# Archive.net
KiCad netlist of a schematic drawn in Altium Designer
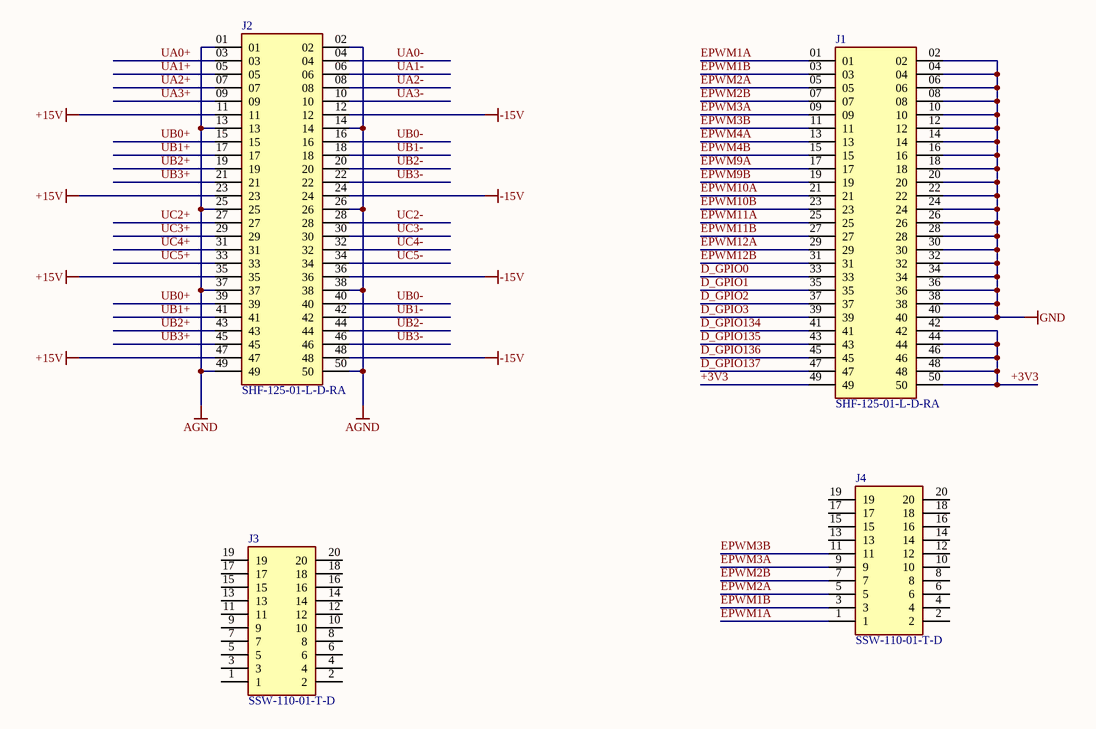
[diagram p0: Archive.SchDoc]

(export (version "E")
  (design (tool "Eeschema 10.0.6"))
  (components
    (comp (ref "J1")
      (value "SHF-125-01-L-D-RA")
      (footprint "SAMTEC_SHF-125-01-L-D-RA")
      (fields (field (name "MF") "Samtec"))
      (libsource (lib "FYP_Connectors") (part "SHF-125-01-L-D-RA"))
    )
    (comp (ref "J2")
      (value "SHF-125-01-L-D-RA")
      (footprint "SAMTEC_SHF-125-01-L-D-RA")
      (fields (field (name "MF") "Samtec"))
      (libsource (lib "FYP_Connectors") (part "SHF-125-01-L-D-RA"))
    )
    (comp (ref "J3")
      (value "SSW-110-01-T-D")
      (footprint "SamacSys:SAMTEC_SSW-110-01-T-D")
      (description "Connector")
      (fields (field (name "MOUSER PART NUMBER") "200-SSW11001TD"))
      (libsource (lib "FYP_Connectors") (part "SSW-110-01-T-D"))
    )
    (comp (ref "J4")
      (value "SSW-110-01-T-D")
      (footprint "SamacSys:SAMTEC_SSW-110-01-T-D")
      (description "Connector")
      (fields (field (name "MOUSER PART NUMBER") "200-SSW11001TD"))
      (libsource (lib "FYP_Connectors") (part "SSW-110-01-T-D"))
    )
  )
  (nets
    (net (code "1") (name "+15V") (class "Default")
      (node (ref "J2") (pin "11") (pinfunction "11_11") (pintype "passive"))
      (node (ref "J2") (pin "23") (pinfunction "23_23") (pintype "passive"))
      (node (ref "J2") (pin "35") (pinfunction "35_35") (pintype "passive"))
      (node (ref "J2") (pin "47") (pinfunction "47_47") (pintype "passive"))
    )
    (net (code "2") (name "-15V") (class "Default")
      (node (ref "J2") (pin "12") (pinfunction "12_12") (pintype "passive"))
      (node (ref "J2") (pin "24") (pinfunction "24_24") (pintype "passive"))
      (node (ref "J2") (pin "36") (pinfunction "36_36") (pintype "passive"))
      (node (ref "J2") (pin "48") (pinfunction "48_48") (pintype "passive"))
    )
    (net (code "3") (name "/+3V3") (class "Default")
      (node (ref "J1") (pin "42") (pinfunction "42_42") (pintype "passive"))
      (node (ref "J1") (pin "44") (pinfunction "44_44") (pintype "passive"))
      (node (ref "J1") (pin "46") (pinfunction "46_46") (pintype "passive"))
      (node (ref "J1") (pin "48") (pinfunction "48_48") (pintype "passive"))
      (node (ref "J1") (pin "49") (pinfunction "49_49") (pintype "passive"))
      (node (ref "J1") (pin "50") (pinfunction "50_50") (pintype "passive"))
    )
    (net (code "4") (name "/D_GPIO0") (class "Default")
      (node (ref "J1") (pin "33") (pinfunction "33_33") (pintype "passive"))
    )
    (net (code "5") (name "/D_GPIO1") (class "Default")
      (node (ref "J1") (pin "35") (pinfunction "35_35") (pintype "passive"))
    )
    (net (code "6") (name "/D_GPIO2") (class "Default")
      (node (ref "J1") (pin "37") (pinfunction "37_37") (pintype "passive"))
    )
    (net (code "7") (name "/D_GPIO3") (class "Default")
      (node (ref "J1") (pin "39") (pinfunction "39_39") (pintype "passive"))
    )
    (net (code "8") (name "/D_GPIO134") (class "Default")
      (node (ref "J1") (pin "41") (pinfunction "41_41") (pintype "passive"))
    )
    (net (code "9") (name "/D_GPIO135") (class "Default")
      (node (ref "J1") (pin "43") (pinfunction "43_43") (pintype "passive"))
    )
    (net (code "10") (name "/D_GPIO136") (class "Default")
      (node (ref "J1") (pin "45") (pinfunction "45_45") (pintype "passive"))
    )
    (net (code "11") (name "/D_GPIO137") (class "Default")
      (node (ref "J1") (pin "47") (pinfunction "47_47") (pintype "passive"))
    )
    (net (code "12") (name "/EPWM1A") (class "Default")
      (node (ref "J1") (pin "01") (pinfunction "01_01") (pintype "passive"))
      (node (ref "J4") (pin "1") (pinfunction "1_1") (pintype "passive"))
    )
    (net (code "13") (name "/EPWM1B") (class "Default")
      (node (ref "J1") (pin "03") (pinfunction "03_03") (pintype "passive"))
      (node (ref "J4") (pin "3") (pinfunction "3_3") (pintype "passive"))
    )
    (net (code "14") (name "/EPWM2A") (class "Default")
      (node (ref "J1") (pin "05") (pinfunction "05_05") (pintype "passive"))
      (node (ref "J4") (pin "5") (pinfunction "5_5") (pintype "passive"))
    )
    (net (code "15") (name "/EPWM2B") (class "Default")
      (node (ref "J1") (pin "07") (pinfunction "07_07") (pintype "passive"))
      (node (ref "J4") (pin "7") (pinfunction "7_7") (pintype "passive"))
    )
    (net (code "16") (name "/EPWM3A") (class "Default")
      (node (ref "J1") (pin "09") (pinfunction "09_09") (pintype "passive"))
      (node (ref "J4") (pin "9") (pinfunction "9_9") (pintype "passive"))
    )
    (net (code "17") (name "/EPWM3B") (class "Default")
      (node (ref "J1") (pin "11") (pinfunction "11_11") (pintype "passive"))
      (node (ref "J4") (pin "11") (pinfunction "11_11") (pintype "passive"))
    )
    (net (code "18") (name "/EPWM4A") (class "Default")
      (node (ref "J1") (pin "13") (pinfunction "13_13") (pintype "passive"))
    )
    (net (code "19") (name "/EPWM4B") (class "Default")
      (node (ref "J1") (pin "15") (pinfunction "15_15") (pintype "passive"))
    )
    (net (code "20") (name "/EPWM9A") (class "Default")
      (node (ref "J1") (pin "17") (pinfunction "17_17") (pintype "passive"))
    )
    (net (code "21") (name "/EPWM9B") (class "Default")
      (node (ref "J1") (pin "19") (pinfunction "19_19") (pintype "passive"))
    )
    (net (code "22") (name "/EPWM10A") (class "Default")
      (node (ref "J1") (pin "21") (pinfunction "21_21") (pintype "passive"))
    )
    (net (code "23") (name "/EPWM10B") (class "Default")
      (node (ref "J1") (pin "23") (pinfunction "23_23") (pintype "passive"))
    )
    (net (code "24") (name "/EPWM11A") (class "Default")
      (node (ref "J1") (pin "25") (pinfunction "25_25") (pintype "passive"))
    )
    (net (code "25") (name "/EPWM11B") (class "Default")
      (node (ref "J1") (pin "27") (pinfunction "27_27") (pintype "passive"))
    )
    (net (code "26") (name "/EPWM12A") (class "Default")
      (node (ref "J1") (pin "29") (pinfunction "29_29") (pintype "passive"))
    )
    (net (code "27") (name "/EPWM12B") (class "Default")
      (node (ref "J1") (pin "31") (pinfunction "31_31") (pintype "passive"))
    )
    (net (code "28") (name "/UA0+") (class "Default")
      (node (ref "J2") (pin "03") (pinfunction "03_03") (pintype "passive"))
    )
    (net (code "29") (name "/UA0-") (class "Default")
      (node (ref "J2") (pin "04") (pinfunction "04_04") (pintype "passive"))
    )
    (net (code "30") (name "/UA1+") (class "Default")
      (node (ref "J2") (pin "05") (pinfunction "05_05") (pintype "passive"))
    )
    (net (code "31") (name "/UA1-") (class "Default")
      (node (ref "J2") (pin "06") (pinfunction "06_06") (pintype "passive"))
    )
    (net (code "32") (name "/UA2+") (class "Default")
      (node (ref "J2") (pin "07") (pinfunction "07_07") (pintype "passive"))
    )
    (net (code "33") (name "/UA2-") (class "Default")
      (node (ref "J2") (pin "08") (pinfunction "08_08") (pintype "passive"))
    )
    (net (code "34") (name "/UA3+") (class "Default")
      (node (ref "J2") (pin "09") (pinfunction "09_09") (pintype "passive"))
    )
    (net (code "35") (name "/UA3-") (class "Default")
      (node (ref "J2") (pin "10") (pinfunction "10_10") (pintype "passive"))
    )
    (net (code "36") (name "/UB0+") (class "Default")
      (node (ref "J2") (pin "15") (pinfunction "15_15") (pintype "passive"))
      (node (ref "J2") (pin "39") (pinfunction "39_39") (pintype "passive"))
    )
    (net (code "37") (name "/UB0-") (class "Default")
      (node (ref "J2") (pin "16") (pinfunction "16_16") (pintype "passive"))
      (node (ref "J2") (pin "40") (pinfunction "40_40") (pintype "passive"))
    )
    (net (code "38") (name "/UB1+") (class "Default")
      (node (ref "J2") (pin "17") (pinfunction "17_17") (pintype "passive"))
      (node (ref "J2") (pin "41") (pinfunction "41_41") (pintype "passive"))
    )
    (net (code "39") (name "/UB1-") (class "Default")
      (node (ref "J2") (pin "18") (pinfunction "18_18") (pintype "passive"))
      (node (ref "J2") (pin "42") (pinfunction "42_42") (pintype "passive"))
    )
    (net (code "40") (name "/UB2+") (class "Default")
      (node (ref "J2") (pin "19") (pinfunction "19_19") (pintype "passive"))
      (node (ref "J2") (pin "43") (pinfunction "43_43") (pintype "passive"))
    )
    (net (code "41") (name "/UB2-") (class "Default")
      (node (ref "J2") (pin "20") (pinfunction "20_20") (pintype "passive"))
      (node (ref "J2") (pin "44") (pinfunction "44_44") (pintype "passive"))
    )
    (net (code "42") (name "/UB3+") (class "Default")
      (node (ref "J2") (pin "21") (pinfunction "21_21") (pintype "passive"))
      (node (ref "J2") (pin "45") (pinfunction "45_45") (pintype "passive"))
    )
    (net (code "43") (name "/UB3-") (class "Default")
      (node (ref "J2") (pin "22") (pinfunction "22_22") (pintype "passive"))
      (node (ref "J2") (pin "46") (pinfunction "46_46") (pintype "passive"))
    )
    (net (code "44") (name "/UC2+") (class "Default")
      (node (ref "J2") (pin "27") (pinfunction "27_27") (pintype "passive"))
    )
    (net (code "45") (name "/UC2-") (class "Default")
      (node (ref "J2") (pin "28") (pinfunction "28_28") (pintype "passive"))
    )
    (net (code "46") (name "/UC3+") (class "Default")
      (node (ref "J2") (pin "29") (pinfunction "29_29") (pintype "passive"))
    )
    (net (code "47") (name "/UC3-") (class "Default")
      (node (ref "J2") (pin "30") (pinfunction "30_30") (pintype "passive"))
    )
    (net (code "48") (name "/UC4+") (class "Default")
      (node (ref "J2") (pin "31") (pinfunction "31_31") (pintype "passive"))
    )
    (net (code "49") (name "/UC4-") (class "Default")
      (node (ref "J2") (pin "32") (pinfunction "32_32") (pintype "passive"))
    )
    (net (code "50") (name "/UC5+") (class "Default")
      (node (ref "J2") (pin "33") (pinfunction "33_33") (pintype "passive"))
    )
    (net (code "51") (name "/UC5-") (class "Default")
      (node (ref "J2") (pin "34") (pinfunction "34_34") (pintype "passive"))
    )
    (net (code "52") (name "AGND") (class "Default")
      (node (ref "J2") (pin "01") (pinfunction "01_01") (pintype "passive"))
      (node (ref "J2") (pin "02") (pinfunction "02_02") (pintype "passive"))
      (node (ref "J2") (pin "13") (pinfunction "13_13") (pintype "passive"))
      (node (ref "J2") (pin "14") (pinfunction "14_14") (pintype "passive"))
      (node (ref "J2") (pin "25") (pinfunction "25_25") (pintype "passive"))
      (node (ref "J2") (pin "26") (pinfunction "26_26") (pintype "passive"))
      (node (ref "J2") (pin "37") (pinfunction "37_37") (pintype "passive"))
      (node (ref "J2") (pin "38") (pinfunction "38_38") (pintype "passive"))
      (node (ref "J2") (pin "49") (pinfunction "49_49") (pintype "passive"))
      (node (ref "J2") (pin "50") (pinfunction "50_50") (pintype "passive"))
    )
    (net (code "53") (name "GND") (class "Default")
      (node (ref "J1") (pin "02") (pinfunction "02_02") (pintype "passive"))
      (node (ref "J1") (pin "04") (pinfunction "04_04") (pintype "passive"))
      (node (ref "J1") (pin "06") (pinfunction "06_06") (pintype "passive"))
      (node (ref "J1") (pin "08") (pinfunction "08_08") (pintype "passive"))
      (node (ref "J1") (pin "10") (pinfunction "10_10") (pintype "passive"))
      (node (ref "J1") (pin "12") (pinfunction "12_12") (pintype "passive"))
      (node (ref "J1") (pin "14") (pinfunction "14_14") (pintype "passive"))
      (node (ref "J1") (pin "16") (pinfunction "16_16") (pintype "passive"))
      (node (ref "J1") (pin "18") (pinfunction "18_18") (pintype "passive"))
      (node (ref "J1") (pin "20") (pinfunction "20_20") (pintype "passive"))
      (node (ref "J1") (pin "22") (pinfunction "22_22") (pintype "passive"))
      (node (ref "J1") (pin "24") (pinfunction "24_24") (pintype "passive"))
      (node (ref "J1") (pin "26") (pinfunction "26_26") (pintype "passive"))
      (node (ref "J1") (pin "28") (pinfunction "28_28") (pintype "passive"))
      (node (ref "J1") (pin "30") (pinfunction "30_30") (pintype "passive"))
      (node (ref "J1") (pin "32") (pinfunction "32_32") (pintype "passive"))
      (node (ref "J1") (pin "34") (pinfunction "34_34") (pintype "passive"))
      (node (ref "J1") (pin "36") (pinfunction "36_36") (pintype "passive"))
      (node (ref "J1") (pin "38") (pinfunction "38_38") (pintype "passive"))
      (node (ref "J1") (pin "40") (pinfunction "40_40") (pintype "passive"))
    )
    (net (code "54") (name "unconnected-(J3-Pad1)") (class "Default")
      (node (ref "J3") (pin "1") (pinfunction "1_1") (pintype "passive"))
    )
    (net (code "55") (name "unconnected-(J3-Pad2)") (class "Default")
      (node (ref "J3") (pin "2") (pinfunction "2_2") (pintype "passive"))
    )
    (net (code "56") (name "unconnected-(J3-Pad3)") (class "Default")
      (node (ref "J3") (pin "3") (pinfunction "3_3") (pintype "passive"))
    )
    (net (code "57") (name "unconnected-(J3-Pad4)") (class "Default")
      (node (ref "J3") (pin "4") (pinfunction "4_4") (pintype "passive"))
    )
    (net (code "58") (name "unconnected-(J3-Pad5)") (class "Default")
      (node (ref "J3") (pin "5") (pinfunction "5_5") (pintype "passive"))
    )
    (net (code "59") (name "unconnected-(J3-Pad6)") (class "Default")
      (node (ref "J3") (pin "6") (pinfunction "6_6") (pintype "passive"))
    )
    (net (code "60") (name "unconnected-(J3-Pad7)") (class "Default")
      (node (ref "J3") (pin "7") (pinfunction "7_7") (pintype "passive"))
    )
    (net (code "61") (name "unconnected-(J3-Pad8)") (class "Default")
      (node (ref "J3") (pin "8") (pinfunction "8_8") (pintype "passive"))
    )
    (net (code "62") (name "unconnected-(J3-Pad9)") (class "Default")
      (node (ref "J3") (pin "9") (pinfunction "9_9") (pintype "passive"))
    )
    (net (code "63") (name "unconnected-(J3-Pad10)") (class "Default")
      (node (ref "J3") (pin "10") (pinfunction "10_10") (pintype "passive"))
    )
    (net (code "64") (name "unconnected-(J3-Pad11)") (class "Default")
      (node (ref "J3") (pin "11") (pinfunction "11_11") (pintype "passive"))
    )
    (net (code "65") (name "unconnected-(J3-Pad12)") (class "Default")
      (node (ref "J3") (pin "12") (pinfunction "12_12") (pintype "passive"))
    )
    (net (code "66") (name "unconnected-(J3-Pad13)") (class "Default")
      (node (ref "J3") (pin "13") (pinfunction "13_13") (pintype "passive"))
    )
    (net (code "67") (name "unconnected-(J3-Pad14)") (class "Default")
      (node (ref "J3") (pin "14") (pinfunction "14_14") (pintype "passive"))
    )
    (net (code "68") (name "unconnected-(J3-Pad15)") (class "Default")
      (node (ref "J3") (pin "15") (pinfunction "15_15") (pintype "passive"))
    )
    (net (code "69") (name "unconnected-(J3-Pad16)") (class "Default")
      (node (ref "J3") (pin "16") (pinfunction "16_16") (pintype "passive"))
    )
    (net (code "70") (name "unconnected-(J3-Pad17)") (class "Default")
      (node (ref "J3") (pin "17") (pinfunction "17_17") (pintype "passive"))
    )
    (net (code "71") (name "unconnected-(J3-Pad18)") (class "Default")
      (node (ref "J3") (pin "18") (pinfunction "18_18") (pintype "passive"))
    )
    (net (code "72") (name "unconnected-(J3-Pad19)") (class "Default")
      (node (ref "J3") (pin "19") (pinfunction "19_19") (pintype "passive"))
    )
    (net (code "73") (name "unconnected-(J3-Pad20)") (class "Default")
      (node (ref "J3") (pin "20") (pinfunction "20_20") (pintype "passive"))
    )
    (net (code "74") (name "unconnected-(J4-Pad2)") (class "Default")
      (node (ref "J4") (pin "2") (pinfunction "2_2") (pintype "passive"))
    )
    (net (code "75") (name "unconnected-(J4-Pad4)") (class "Default")
      (node (ref "J4") (pin "4") (pinfunction "4_4") (pintype "passive"))
    )
    (net (code "76") (name "unconnected-(J4-Pad6)") (class "Default")
      (node (ref "J4") (pin "6") (pinfunction "6_6") (pintype "passive"))
    )
    (net (code "77") (name "unconnected-(J4-Pad8)") (class "Default")
      (node (ref "J4") (pin "8") (pinfunction "8_8") (pintype "passive"))
    )
    (net (code "78") (name "unconnected-(J4-Pad10)") (class "Default")
      (node (ref "J4") (pin "10") (pinfunction "10_10") (pintype "passive"))
    )
    (net (code "79") (name "unconnected-(J4-Pad12)") (class "Default")
      (node (ref "J4") (pin "12") (pinfunction "12_12") (pintype "passive"))
    )
    (net (code "80") (name "unconnected-(J4-Pad13)") (class "Default")
      (node (ref "J4") (pin "13") (pinfunction "13_13") (pintype "passive"))
    )
    (net (code "81") (name "unconnected-(J4-Pad14)") (class "Default")
      (node (ref "J4") (pin "14") (pinfunction "14_14") (pintype "passive"))
    )
    (net (code "82") (name "unconnected-(J4-Pad15)") (class "Default")
      (node (ref "J4") (pin "15") (pinfunction "15_15") (pintype "passive"))
    )
    (net (code "83") (name "unconnected-(J4-Pad16)") (class "Default")
      (node (ref "J4") (pin "16") (pinfunction "16_16") (pintype "passive"))
    )
    (net (code "84") (name "unconnected-(J4-Pad17)") (class "Default")
      (node (ref "J4") (pin "17") (pinfunction "17_17") (pintype "passive"))
    )
    (net (code "85") (name "unconnected-(J4-Pad18)") (class "Default")
      (node (ref "J4") (pin "18") (pinfunction "18_18") (pintype "passive"))
    )
    (net (code "86") (name "unconnected-(J4-Pad19)") (class "Default")
      (node (ref "J4") (pin "19") (pinfunction "19_19") (pintype "passive"))
    )
    (net (code "87") (name "unconnected-(J4-Pad20)") (class "Default")
      (node (ref "J4") (pin "20") (pinfunction "20_20") (pintype "passive"))
    )
  )
)
